# LightController.net
KiCad netlist of a schematic drawn in EAGLE
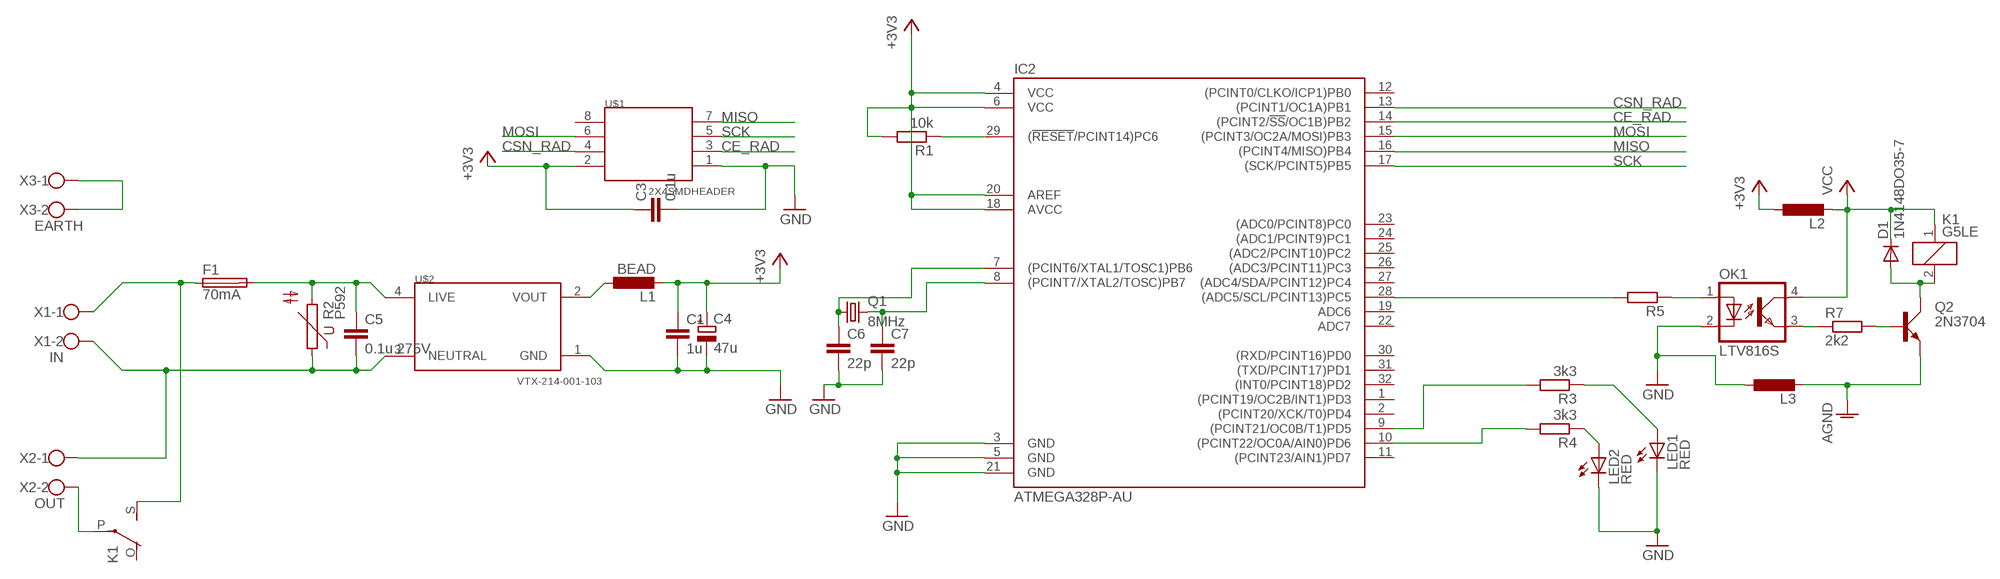
[diagram p0: schematic, sheet 1]

(export (version "E")
  (design (tool "Eeschema 10.0.6"))
  (components
    (comp (ref "C1")
      (value "1u")
      (footprint "eagle-import:C1206K")
      (libsource (lib "eagle-import") (part "C-EUC1206K"))
    )
    (comp (ref "C3")
      (value "0.1u")
      (footprint "eagle-import:C1206")
      (libsource (lib "eagle-import") (part "C-EUC1206"))
    )
    (comp (ref "C4")
      (value "47u")
      (footprint "eagle-import:E2,5-6E")
      (libsource (lib "eagle-import") (part "CPOL-EUE2,5-6E"))
    )
    (comp (ref "C5")
      (value "0.1u 275V")
      (footprint "eagle-import:C15B5")
      (libsource (lib "eagle-import") (part "C15/5"))
    )
    (comp (ref "C6")
      (value "22p")
      (footprint "eagle-import:C1206")
      (libsource (lib "eagle-import") (part "C-EUC1206"))
    )
    (comp (ref "C7")
      (value "22p")
      (footprint "eagle-import:C1206")
      (libsource (lib "eagle-import") (part "C-EUC1206"))
    )
    (comp (ref "D1")
      (value "1N4148DO35-7")
      (footprint "eagle-import:DO35-7")
      (libsource (lib "eagle-import") (part "1N4148DO35-7"))
    )
    (comp (ref "F1")
      (value "70mA")
      (footprint "eagle-import:SH22,5A")
      (libsource (lib "eagle-import") (part "FUSESH22,5A"))
    )
    (comp (ref "IC2")
      (value "ATMEGA328P-AU")
      (footprint "eagle-import:TQFP32-08")
      (libsource (lib "eagle-import") (part "ATMEGA328P-AU"))
    )
    (comp (ref "K1")
      (value "G5LE")
      (footprint "eagle-import:G5LE")
      (libsource (lib "eagle-import") (part "G5LE"))
    )
    (comp (ref "L1")
      (value "BEAD")
      (footprint "eagle-import:L3230M")
      (libsource (lib "eagle-import") (part "L-EUL3230M"))
    )
    (comp (ref "L2")
      (value "L-EUL3230M")
      (footprint "eagle-import:L3230M")
      (libsource (lib "eagle-import") (part "L-EUL3230M"))
    )
    (comp (ref "L3")
      (value "L-EUL3230M")
      (footprint "eagle-import:L3230M")
      (libsource (lib "eagle-import") (part "L-EUL3230M"))
    )
    (comp (ref "LED1")
      (value "RED")
      (footprint "eagle-import:1206")
      (libsource (lib "eagle-import") (part "LEDSMT1206"))
    )
    (comp (ref "LED2")
      (value "RED")
      (footprint "eagle-import:1206")
      (libsource (lib "eagle-import") (part "LEDSMT1206"))
    )
    (comp (ref "OK1")
      (value "LTV816S")
      (footprint "eagle-import:DIL4-SMD")
      (libsource (lib "eagle-import") (part "LTV816S"))
    )
    (comp (ref "Q1")
      (value "8MHz")
      (footprint "eagle-import:HC49U70")
      (libsource (lib "eagle-import") (part "CRYSTALHC49U70"))
    )
    (comp (ref "Q2")
      (value "2N3704")
      (footprint "eagle-import:TO92C")
      (libsource (lib "eagle-import") (part "2N3704"))
    )
    (comp (ref "R1")
      (value "10k")
      (footprint "eagle-import:R1206")
      (libsource (lib "eagle-import") (part "R-EU_R1206"))
    )
    (comp (ref "R2")
      (value "P592")
      (footprint "eagle-import:P592")
      (libsource (lib "eagle-import") (part "P592"))
    )
    (comp (ref "R3")
      (value "3k3")
      (footprint "eagle-import:R1206")
      (libsource (lib "eagle-import") (part "R-EU_R1206"))
    )
    (comp (ref "R4")
      (value "3k3")
      (footprint "eagle-import:R1206")
      (libsource (lib "eagle-import") (part "R-EU_R1206"))
    )
    (comp (ref "R5")
      (value "R-EU_R1206")
      (footprint "eagle-import:R1206")
      (libsource (lib "eagle-import") (part "R-EU_R1206"))
    )
    (comp (ref "R7")
      (value "2k2")
      (footprint "eagle-import:R1206")
      (libsource (lib "eagle-import") (part "R-EU_R1206"))
    )
    (comp (ref "U$1")
      (value "2X4SMDHEADER")
      (footprint "eagle-import:TSM-110-XX-XXX-DV")
      (libsource (lib "eagle-import") (part "2X4SMDHEADER"))
    )
    (comp (ref "U$2")
      (value "VTX-214-001-103")
      (footprint "eagle-import:VTX214001103")
      (libsource (lib "eagle-import") (part "VTX-214-001-103"))
    )
    (comp (ref "X1")
      (value "IN")
      (footprint "eagle-import:W237-102")
      (fields (field (name "MPN") "237-102"))
      (libsource (lib "eagle-import") (part "W237-102"))
    )
    (comp (ref "X2")
      (value "OUT")
      (footprint "eagle-import:W237-102")
      (fields (field (name "MPN") "237-102"))
      (libsource (lib "eagle-import") (part "W237-102"))
    )
    (comp (ref "X3")
      (value "EARTH")
      (footprint "eagle-import:W237-102")
      (fields (field (name "MPN") "237-102"))
      (libsource (lib "eagle-import") (part "W237-102"))
    )
  )
  (nets
    (net (code "1") (name "+3V3") (class "Default")
      (node (ref "C1") (pin "1") (pinfunction "1_1") (pintype "passive"))
      (node (ref "C3") (pin "1") (pinfunction "1_1") (pintype "passive"))
      (node (ref "C4") (pin "+") (pinfunction "+_+") (pintype "passive"))
      (node (ref "IC2") (pin "18") (pinfunction "AVCC_18") (pintype "bidirectional"))
      (node (ref "IC2") (pin "20") (pinfunction "AREF_20") (pintype "bidirectional"))
      (node (ref "IC2") (pin "4") (pinfunction "VCC_4") (pintype "bidirectional"))
      (node (ref "IC2") (pin "6") (pinfunction "VCC_6") (pintype "bidirectional"))
      (node (ref "L1") (pin "2") (pinfunction "2_2") (pintype "passive"))
      (node (ref "L2") (pin "1") (pinfunction "1_1") (pintype "passive"))
      (node (ref "R1") (pin "2") (pinfunction "2_2") (pintype "passive"))
      (node (ref "U$1") (pin "2") (pinfunction "2_2") (pintype "bidirectional"))
    )
    (net (code "2") (name "/CE_RAD") (class "Default")
      (node (ref "IC2") (pin "14") (pinfunction "(PCINT2/~{SS}/OC1B)PB2_14") (pintype "bidirectional"))
      (node (ref "U$1") (pin "3") (pinfunction "3_3") (pintype "bidirectional"))
    )
    (net (code "3") (name "/CSN_RAD") (class "Default")
      (node (ref "IC2") (pin "13") (pinfunction "(PCINT1/OC1A)PB1_13") (pintype "bidirectional"))
      (node (ref "U$1") (pin "4") (pinfunction "4_4") (pintype "bidirectional"))
    )
    (net (code "4") (name "/MISO") (class "Default")
      (node (ref "IC2") (pin "16") (pinfunction "(PCINT4/MISO)PB4_16") (pintype "bidirectional"))
      (node (ref "U$1") (pin "7") (pinfunction "7_7") (pintype "bidirectional"))
    )
    (net (code "5") (name "/MOSI") (class "Default")
      (node (ref "IC2") (pin "15") (pinfunction "(PCINT3/OC2A/MOSI)PB3_15") (pintype "bidirectional"))
      (node (ref "U$1") (pin "6") (pinfunction "6_6") (pintype "bidirectional"))
    )
    (net (code "6") (name "/SCK") (class "Default")
      (node (ref "IC2") (pin "17") (pinfunction "(SCK/PCINT5)PB5_17") (pintype "bidirectional"))
      (node (ref "U$1") (pin "5") (pinfunction "5_5") (pintype "bidirectional"))
    )
    (net (code "7") (name "AGND") (class "Default")
      (node (ref "L3") (pin "2") (pinfunction "2_2") (pintype "passive"))
      (node (ref "Q2") (pin "E") (pinfunction "E_E") (pintype "passive"))
    )
    (net (code "8") (name "GND") (class "Default")
      (node (ref "C1") (pin "2") (pinfunction "2_2") (pintype "passive"))
      (node (ref "C3") (pin "2") (pinfunction "2_2") (pintype "passive"))
      (node (ref "C4") (pin "-") (pinfunction "-_-") (pintype "passive"))
      (node (ref "C6") (pin "2") (pinfunction "2_2") (pintype "passive"))
      (node (ref "C7") (pin "2") (pinfunction "2_2") (pintype "passive"))
      (node (ref "IC2") (pin "21") (pinfunction "GND_21") (pintype "bidirectional"))
      (node (ref "IC2") (pin "3") (pinfunction "GND_3") (pintype "bidirectional"))
      (node (ref "IC2") (pin "5") (pinfunction "GND_5") (pintype "bidirectional"))
      (node (ref "L3") (pin "1") (pinfunction "1_1") (pintype "passive"))
      (node (ref "LED1") (pin "C") (pinfunction "C_C") (pintype "passive"))
      (node (ref "LED2") (pin "C") (pinfunction "C_C") (pintype "passive"))
      (node (ref "OK1") (pin "2") (pinfunction "C_2") (pintype "passive"))
      (node (ref "U$1") (pin "1") (pinfunction "1_1") (pintype "bidirectional"))
      (node (ref "U$2") (pin "1") (pinfunction "GND_1") (pintype "power_in"))
    )
    (net (code "9") (name "Net-(D1-PadA)") (class "Default")
      (node (ref "D1") (pin "A") (pinfunction "A_A") (pintype "passive"))
      (node (ref "K1") (pin "2") (pinfunction "2_2") (pintype "passive"))
      (node (ref "Q2") (pin "C") (pinfunction "C_C") (pintype "passive"))
    )
    (net (code "10") (name "Net-(IC2-(ADC5{slash}SCL{slash}PCINT13)PC5)") (class "Default")
      (node (ref "IC2") (pin "28") (pinfunction "(ADC5/SCL/PCINT13)PC5_28") (pintype "bidirectional"))
      (node (ref "R5") (pin "2") (pinfunction "2_2") (pintype "passive"))
    )
    (net (code "11") (name "Net-(IC2-(PCINT6{slash}XTAL1{slash}TOSC1)PB6)") (class "Default")
      (node (ref "C6") (pin "1") (pinfunction "1_1") (pintype "passive"))
      (node (ref "IC2") (pin "7") (pinfunction "(PCINT6/XTAL1/TOSC1)PB6_7") (pintype "bidirectional"))
      (node (ref "Q1") (pin "1") (pinfunction "1_1") (pintype "passive"))
    )
    (net (code "12") (name "Net-(IC2-(PCINT7{slash}XTAL2{slash}TOSC)PB7)") (class "Default")
      (node (ref "C7") (pin "1") (pinfunction "1_1") (pintype "passive"))
      (node (ref "IC2") (pin "8") (pinfunction "(PCINT7/XTAL2/TOSC)PB7_8") (pintype "bidirectional"))
      (node (ref "Q1") (pin "2") (pinfunction "2_2") (pintype "passive"))
    )
    (net (code "13") (name "Net-(IC2-(PCINT21{slash}OC0B{slash}T1)PD5)") (class "Default")
      (node (ref "IC2") (pin "9") (pinfunction "(PCINT21/OC0B/T1)PD5_9") (pintype "bidirectional"))
      (node (ref "R3") (pin "2") (pinfunction "2_2") (pintype "passive"))
    )
    (net (code "14") (name "Net-(IC2-(PCINT22{slash}OC0A{slash}AIN0)PD6)") (class "Default")
      (node (ref "IC2") (pin "10") (pinfunction "(PCINT22/OC0A/AIN0)PD6_10") (pintype "bidirectional"))
      (node (ref "R4") (pin "2") (pinfunction "2_2") (pintype "passive"))
    )
    (net (code "15") (name "Net-(IC2-(~{RESET}{slash}PCINT14)PC6)") (class "Default")
      (node (ref "IC2") (pin "29") (pinfunction "(~{RESET}/PCINT14)PC6_29") (pintype "bidirectional"))
      (node (ref "R1") (pin "1") (pinfunction "1_1") (pintype "passive"))
    )
    (net (code "16") (name "Net-(LED1-PadA)") (class "Default")
      (node (ref "LED1") (pin "A") (pinfunction "A_A") (pintype "passive"))
      (node (ref "R3") (pin "1") (pinfunction "1_1") (pintype "passive"))
    )
    (net (code "17") (name "Net-(LED2-PadA)") (class "Default")
      (node (ref "LED2") (pin "A") (pinfunction "A_A") (pintype "passive"))
      (node (ref "R4") (pin "1") (pinfunction "1_1") (pintype "passive"))
    )
    (net (code "18") (name "Net-(OK1-A)") (class "Default")
      (node (ref "OK1") (pin "1") (pinfunction "A_1") (pintype "passive"))
      (node (ref "R5") (pin "1") (pinfunction "1_1") (pintype "passive"))
    )
    (net (code "19") (name "Net-(OK1-EMIT)") (class "Default")
      (node (ref "OK1") (pin "3") (pinfunction "EMIT_3") (pintype "passive"))
      (node (ref "R7") (pin "1") (pinfunction "1_1") (pintype "passive"))
    )
    (net (code "20") (name "Net-(Q2-PadB)") (class "Default")
      (node (ref "Q2") (pin "B") (pinfunction "B_B") (pintype "passive"))
      (node (ref "R7") (pin "2") (pinfunction "2_2") (pintype "passive"))
    )
    (net (code "21") (name "Net-(U$2-LIVE)") (class "Default")
      (node (ref "C5") (pin "1") (pinfunction "1_1") (pintype "passive"))
      (node (ref "F1") (pin "2") (pinfunction "2_2") (pintype "passive"))
      (node (ref "R2") (pin "2") (pinfunction "2_2") (pintype "passive"))
      (node (ref "U$2") (pin "4") (pinfunction "LIVE_4") (pintype "input"))
    )
    (net (code "22") (name "Net-(U$2-NEUTRAL)") (class "Default")
      (node (ref "C5") (pin "2") (pinfunction "2_2") (pintype "passive"))
      (node (ref "R2") (pin "1") (pinfunction "1_1") (pintype "passive"))
      (node (ref "U$2") (pin "3") (pinfunction "NEUTRAL_3") (pintype "input"))
      (node (ref "X1") (pin "2") (pinfunction "KL_2") (pintype "passive"))
      (node (ref "X2") (pin "1") (pinfunction "KL_1") (pintype "passive"))
    )
    (net (code "23") (name "Net-(U$2-VOUT)") (class "Default")
      (node (ref "L1") (pin "1") (pinfunction "1_1") (pintype "passive"))
      (node (ref "U$2") (pin "2") (pinfunction "VOUT_2") (pintype "power_in"))
    )
    (net (code "24") (name "Net-(X1A-KL)") (class "Default")
      (node (ref "F1") (pin "1") (pinfunction "1_1") (pintype "passive"))
      (node (ref "K1") (pin "S") (pinfunction "S_S") (pintype "passive"))
      (node (ref "X1") (pin "1") (pinfunction "KL_1") (pintype "passive"))
    )
    (net (code "25") (name "Net-(X2B-KL)") (class "Default")
      (node (ref "K1") (pin "P") (pinfunction "P_P") (pintype "passive"))
      (node (ref "X2") (pin "2") (pinfunction "KL_2") (pintype "passive"))
    )
    (net (code "26") (name "Net-(X3A-KL)") (class "Default")
      (node (ref "X3") (pin "1") (pinfunction "KL_1") (pintype "passive"))
      (node (ref "X3") (pin "2") (pinfunction "KL_2") (pintype "passive"))
    )
    (net (code "27") (name "VCC") (class "Default")
      (node (ref "D1") (pin "C") (pinfunction "C_C") (pintype "passive"))
      (node (ref "K1") (pin "1") (pinfunction "1_1") (pintype "passive"))
      (node (ref "L2") (pin "2") (pinfunction "2_2") (pintype "passive"))
      (node (ref "OK1") (pin "4") (pinfunction "COL_4") (pintype "passive"))
    )
    (net (code "28") (name "unconnected-(IC2-(ADC0{slash}PCINT8)PC0-Pad23)") (class "Default")
      (node (ref "IC2") (pin "23") (pinfunction "(ADC0/PCINT8)PC0_23") (pintype "bidirectional"))
    )
    (net (code "29") (name "unconnected-(IC2-(ADC1{slash}PCINT9)PC1-Pad24)") (class "Default")
      (node (ref "IC2") (pin "24") (pinfunction "(ADC1/PCINT9)PC1_24") (pintype "bidirectional"))
    )
    (net (code "30") (name "unconnected-(IC2-(ADC2{slash}PCINT10)PC2-Pad25)") (class "Default")
      (node (ref "IC2") (pin "25") (pinfunction "(ADC2/PCINT10)PC2_25") (pintype "bidirectional"))
    )
    (net (code "31") (name "unconnected-(IC2-(ADC3{slash}PCINT11)PC3-Pad26)") (class "Default")
      (node (ref "IC2") (pin "26") (pinfunction "(ADC3/PCINT11)PC3_26") (pintype "bidirectional"))
    )
    (net (code "32") (name "unconnected-(IC2-(ADC4{slash}SDA{slash}PCINT12)PC4-Pad27)") (class "Default")
      (node (ref "IC2") (pin "27") (pinfunction "(ADC4/SDA/PCINT12)PC4_27") (pintype "bidirectional"))
    )
    (net (code "33") (name "unconnected-(IC2-(INT0{slash}PCINT18)PD2-Pad32)") (class "Default")
      (node (ref "IC2") (pin "32") (pinfunction "(INT0/PCINT18)PD2_32") (pintype "bidirectional"))
    )
    (net (code "34") (name "unconnected-(IC2-(PCINT0{slash}CLKO{slash}ICP1)PB0-Pad12)") (class "Default")
      (node (ref "IC2") (pin "12") (pinfunction "(PCINT0/CLKO/ICP1)PB0_12") (pintype "bidirectional"))
    )
    (net (code "35") (name "unconnected-(IC2-(PCINT19{slash}OC2B{slash}INT1)PD3-Pad1)") (class "Default")
      (node (ref "IC2") (pin "1") (pinfunction "(PCINT19/OC2B/INT1)PD3_1") (pintype "bidirectional"))
    )
    (net (code "36") (name "unconnected-(IC2-(PCINT20{slash}XCK{slash}T0)PD4-Pad2)") (class "Default")
      (node (ref "IC2") (pin "2") (pinfunction "(PCINT20/XCK/T0)PD4_2") (pintype "bidirectional"))
    )
    (net (code "37") (name "unconnected-(IC2-(PCINT23{slash}AIN1)PD7-Pad11)") (class "Default")
      (node (ref "IC2") (pin "11") (pinfunction "(PCINT23/AIN1)PD7_11") (pintype "bidirectional"))
    )
    (net (code "38") (name "unconnected-(IC2-(RXD{slash}PCINT16)PD0-Pad30)") (class "Default")
      (node (ref "IC2") (pin "30") (pinfunction "(RXD/PCINT16)PD0_30") (pintype "bidirectional"))
    )
    (net (code "39") (name "unconnected-(IC2-(TXD{slash}PCINT17)PD1-Pad31)") (class "Default")
      (node (ref "IC2") (pin "31") (pinfunction "(TXD/PCINT17)PD1_31") (pintype "bidirectional"))
    )
    (net (code "40") (name "unconnected-(IC2-ADC6-Pad19)") (class "Default")
      (node (ref "IC2") (pin "19") (pinfunction "ADC6_19") (pintype "bidirectional"))
    )
    (net (code "41") (name "unconnected-(IC2-ADC7-Pad22)") (class "Default")
      (node (ref "IC2") (pin "22") (pinfunction "ADC7_22") (pintype "bidirectional"))
    )
    (net (code "42") (name "unconnected-(K1-PadO)") (class "Default")
      (node (ref "K1") (pin "O") (pinfunction "O_O") (pintype "passive"))
    )
    (net (code "43") (name "unconnected-(U$1-Pad8)") (class "Default")
      (node (ref "U$1") (pin "8") (pinfunction "8_8") (pintype "bidirectional"))
    )
  )
)
